# LEDMatrix_V1_0.net
KiCad netlist of a schematic drawn in EAGLE
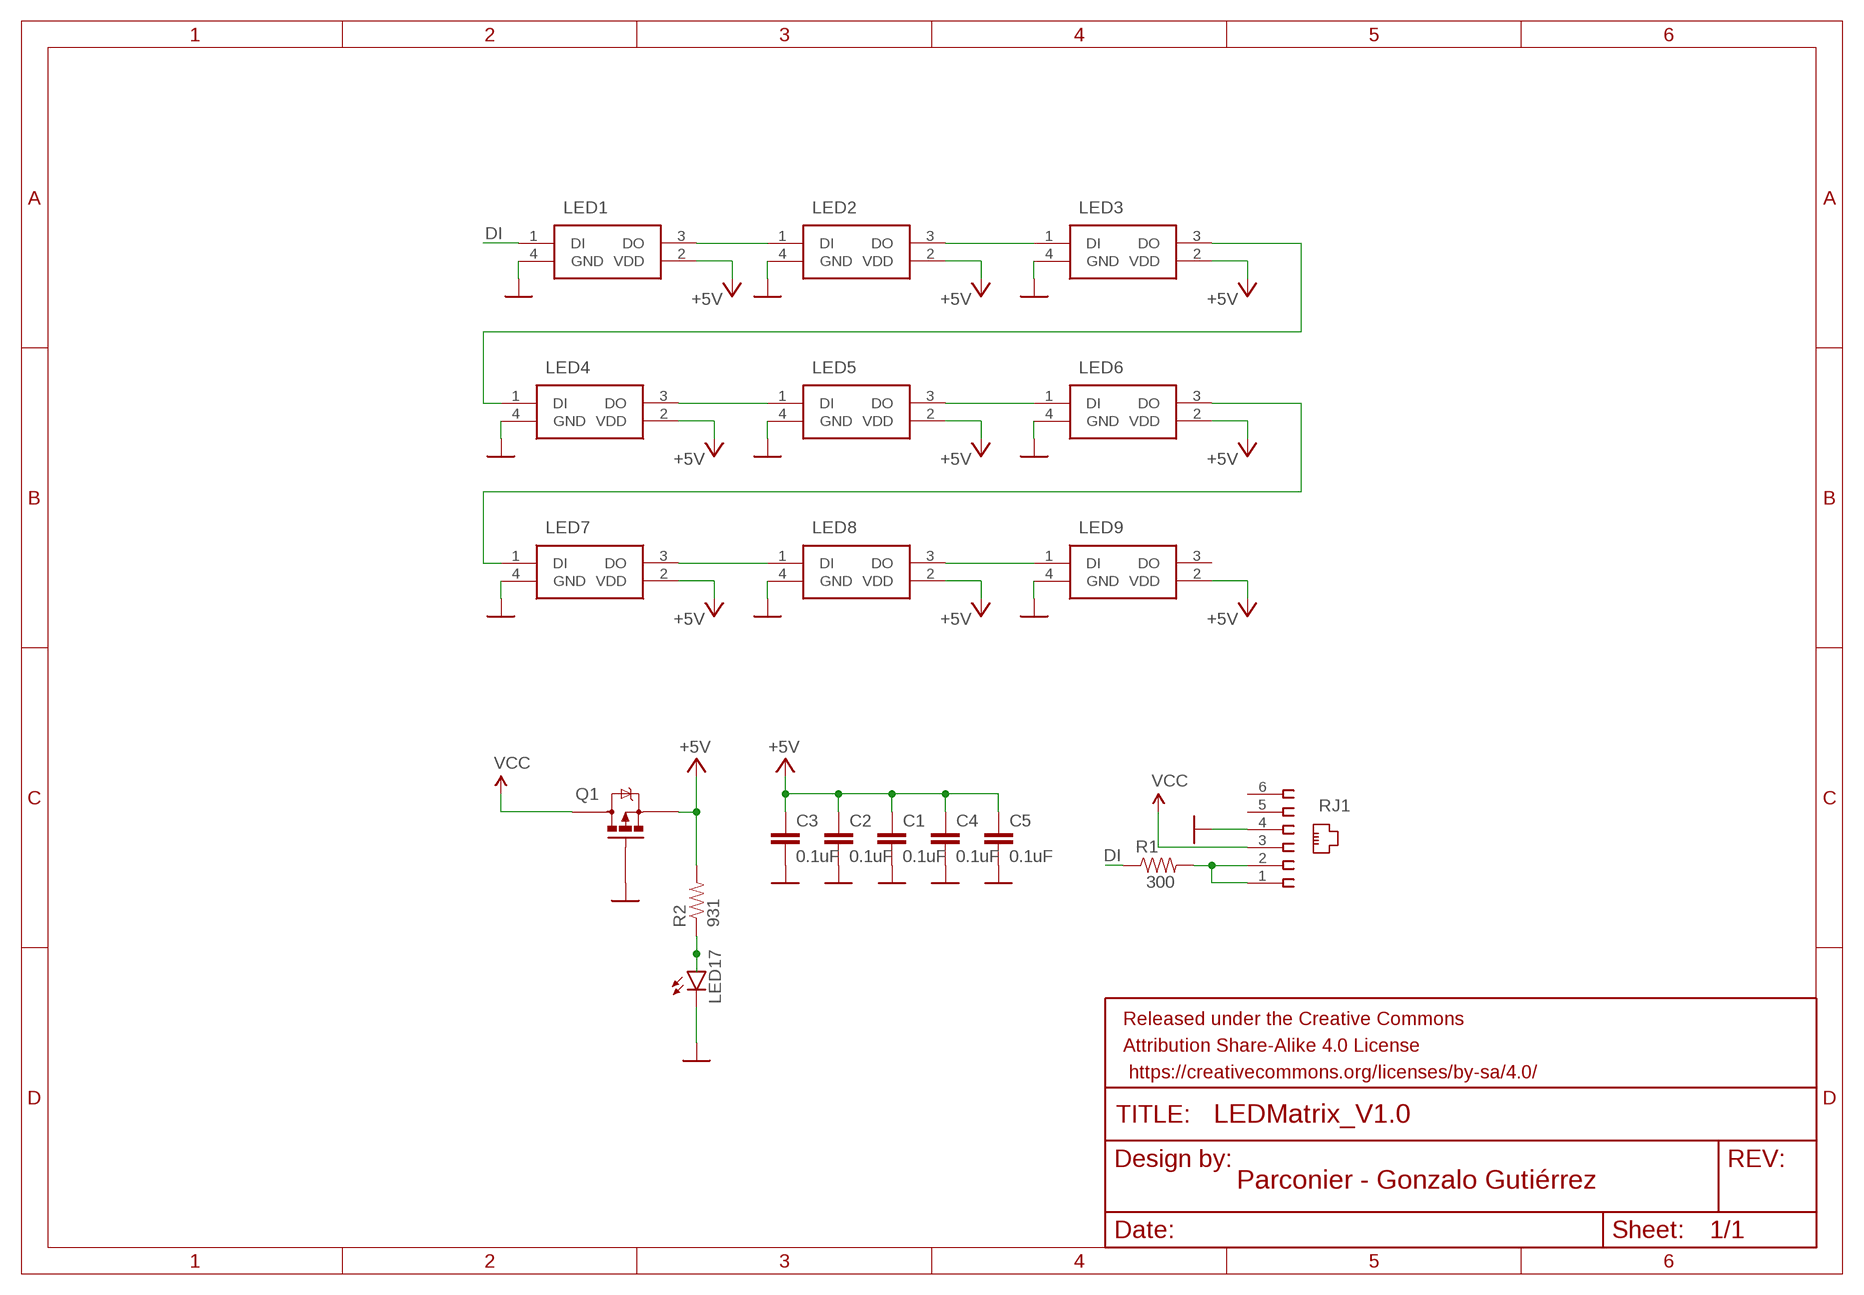
[diagram p0: schematic, sheet 1]

(export (version "E")
  (design (tool "Eeschema 10.0.6"))
  (components
    (comp (ref "C1")
      (value "0.1uF")
      (footprint "eagle-import:0402")
      (fields (field (name "MPN") "CC0402KRX5R9BB104"))
      (libsource (lib "eagle-import") (part "CAP_0402"))
    )
    (comp (ref "C2")
      (value "0.1uF")
      (footprint "eagle-import:0402")
      (fields (field (name "MPN") "CC0402KRX5R9BB104"))
      (libsource (lib "eagle-import") (part "CAP_0402"))
    )
    (comp (ref "C3")
      (value "0.1uF")
      (footprint "eagle-import:0402")
      (fields (field (name "MPN") "CC0402KRX5R9BB104"))
      (libsource (lib "eagle-import") (part "CAP_0402"))
    )
    (comp (ref "C4")
      (value "0.1uF")
      (footprint "eagle-import:0402")
      (fields (field (name "MPN") "CC0402KRX5R9BB104"))
      (libsource (lib "eagle-import") (part "CAP_0402"))
    )
    (comp (ref "C5")
      (value "0.1uF")
      (footprint "eagle-import:0402")
      (fields (field (name "MPN") "CC0402KRX5R9BB104"))
      (libsource (lib "eagle-import") (part "CAP_0402"))
    )
    (comp (ref "LED1")
      (value "SK6812MINI")
      (footprint "eagle-import:SK6812MINI")
      (fields (field (name "SPICEPREFIX") "E"))
      (libsource (lib "eagle-import") (part "SK6812MINI"))
    )
    (comp (ref "LED2")
      (value "SK6812MINI")
      (footprint "eagle-import:SK6812MINI")
      (fields (field (name "SPICEPREFIX") "E"))
      (libsource (lib "eagle-import") (part "SK6812MINI"))
    )
    (comp (ref "LED3")
      (value "SK6812MINI")
      (footprint "eagle-import:SK6812MINI")
      (fields (field (name "SPICEPREFIX") "E"))
      (libsource (lib "eagle-import") (part "SK6812MINI"))
    )
    (comp (ref "LED4")
      (value "SK6812MINI")
      (footprint "eagle-import:SK6812MINI")
      (fields (field (name "SPICEPREFIX") "E"))
      (libsource (lib "eagle-import") (part "SK6812MINI"))
    )
    (comp (ref "LED5")
      (value "SK6812MINI")
      (footprint "eagle-import:SK6812MINI")
      (fields (field (name "SPICEPREFIX") "E"))
      (libsource (lib "eagle-import") (part "SK6812MINI"))
    )
    (comp (ref "LED6")
      (value "SK6812MINI")
      (footprint "eagle-import:SK6812MINI")
      (fields (field (name "SPICEPREFIX") "E"))
      (libsource (lib "eagle-import") (part "SK6812MINI"))
    )
    (comp (ref "LED7")
      (value "SK6812MINI")
      (footprint "eagle-import:SK6812MINI")
      (fields (field (name "SPICEPREFIX") "E"))
      (libsource (lib "eagle-import") (part "SK6812MINI"))
    )
    (comp (ref "LED8")
      (value "SK6812MINI")
      (footprint "eagle-import:SK6812MINI")
      (fields (field (name "SPICEPREFIX") "E"))
      (libsource (lib "eagle-import") (part "SK6812MINI"))
    )
    (comp (ref "LED9")
      (value "SK6812MINI")
      (footprint "eagle-import:SK6812MINI")
      (fields (field (name "SPICEPREFIX") "E"))
      (libsource (lib "eagle-import") (part "SK6812MINI"))
    )
    (comp (ref "LED17")
      (value "LED0603")
      (footprint "eagle-import:LED-0603")
      (fields (field (name "MPN") "LTST-C193KRKT-5A "))
      (libsource (lib "eagle-import") (part "LED0603"))
    )
    (comp (ref "Q1")
      (value "IRLML2244TRPBF")
      (footprint "eagle-import:SOT95P237X112-3N")
      (description "HEXFET Power MOSFET")
      (fields
        (field (name "ARROW_PART_NUMBER") "IRLML2244TRPBF")
        (field (name "HEIGHT") "mm")
        (field (name "MANUFACTURER_NAME") "International Rectifier")
        (field (name "MANUFACTURER_PART_NUMBER") "IRLML2244TRPBF")
      )
      (libsource (lib "eagle-import") (part "IRLML2244TRPBF"))
    )
    (comp (ref "R1")
      (value "300")
      (footprint "eagle-import:RESC1005X35")
      (fields (field (name "MPN") "RC0402JR-07300RL"))
      (libsource (lib "eagle-import") (part "RES_0402"))
    )
    (comp (ref "R2")
      (value "931")
      (footprint "eagle-import:RESC1005X35")
      (fields (field (name "MPN") "RC0402FR-07931RL"))
      (libsource (lib "eagle-import") (part "RES_0402"))
    )
    (comp (ref "RJ1")
      (value "615006138421")
      (footprint "eagle-import:615006138421")
      (fields (field (name "RS_PART_NUMBER") "7350282"))
      (libsource (lib "eagle-import") (part "615006138421"))
    )
  )
  (nets
    (net (code "1") (name "+5V") (class "Default")
      (node (ref "C1") (pin "1") (pinfunction "1_1") (pintype "passive"))
      (node (ref "C2") (pin "1") (pinfunction "1_1") (pintype "passive"))
      (node (ref "C3") (pin "1") (pinfunction "1_1") (pintype "passive"))
      (node (ref "C4") (pin "1") (pinfunction "1_1") (pintype "passive"))
      (node (ref "C5") (pin "1") (pinfunction "1_1") (pintype "passive"))
      (node (ref "LED1") (pin "2") (pinfunction "VDD_2") (pintype "bidirectional"))
      (node (ref "LED2") (pin "2") (pinfunction "VDD_2") (pintype "bidirectional"))
      (node (ref "LED3") (pin "2") (pinfunction "VDD_2") (pintype "bidirectional"))
      (node (ref "LED4") (pin "2") (pinfunction "VDD_2") (pintype "bidirectional"))
      (node (ref "LED5") (pin "2") (pinfunction "VDD_2") (pintype "bidirectional"))
      (node (ref "LED6") (pin "2") (pinfunction "VDD_2") (pintype "bidirectional"))
      (node (ref "LED7") (pin "2") (pinfunction "VDD_2") (pintype "bidirectional"))
      (node (ref "LED8") (pin "2") (pinfunction "VDD_2") (pintype "bidirectional"))
      (node (ref "LED9") (pin "2") (pinfunction "VDD_2") (pintype "bidirectional"))
      (node (ref "Q1") (pin "2") (pinfunction "S_2") (pintype "bidirectional"))
      (node (ref "R2") (pin "2") (pinfunction "2_2") (pintype "passive"))
    )
    (net (code "2") (name "/DI") (class "Default")
      (node (ref "LED1") (pin "1") (pinfunction "DI_1") (pintype "bidirectional"))
      (node (ref "R1") (pin "1") (pinfunction "1_1") (pintype "passive"))
    )
    (net (code "3") (name "GND") (class "Default")
      (node (ref "C1") (pin "2") (pinfunction "2_2") (pintype "passive"))
      (node (ref "C2") (pin "2") (pinfunction "2_2") (pintype "passive"))
      (node (ref "C3") (pin "2") (pinfunction "2_2") (pintype "passive"))
      (node (ref "C4") (pin "2") (pinfunction "2_2") (pintype "passive"))
      (node (ref "C5") (pin "2") (pinfunction "2_2") (pintype "passive"))
      (node (ref "LED1") (pin "4") (pinfunction "GND_4") (pintype "bidirectional"))
      (node (ref "LED17") (pin "C") (pinfunction "C_C") (pintype "passive"))
      (node (ref "LED2") (pin "4") (pinfunction "GND_4") (pintype "bidirectional"))
      (node (ref "LED3") (pin "4") (pinfunction "GND_4") (pintype "bidirectional"))
      (node (ref "LED4") (pin "4") (pinfunction "GND_4") (pintype "bidirectional"))
      (node (ref "LED5") (pin "4") (pinfunction "GND_4") (pintype "bidirectional"))
      (node (ref "LED6") (pin "4") (pinfunction "GND_4") (pintype "bidirectional"))
      (node (ref "LED7") (pin "4") (pinfunction "GND_4") (pintype "bidirectional"))
      (node (ref "LED8") (pin "4") (pinfunction "GND_4") (pintype "bidirectional"))
      (node (ref "LED9") (pin "4") (pinfunction "GND_4") (pintype "bidirectional"))
      (node (ref "Q1") (pin "1") (pinfunction "G_1") (pintype "bidirectional"))
      (node (ref "RJ1") (pin "4") (pinfunction "4_4") (pintype "input"))
    )
    (net (code "4") (name "Net-(LED1-DO)") (class "Default")
      (node (ref "LED1") (pin "3") (pinfunction "DO_3") (pintype "bidirectional"))
      (node (ref "LED2") (pin "1") (pinfunction "DI_1") (pintype "bidirectional"))
    )
    (net (code "5") (name "Net-(LED2-DO)") (class "Default")
      (node (ref "LED2") (pin "3") (pinfunction "DO_3") (pintype "bidirectional"))
      (node (ref "LED3") (pin "1") (pinfunction "DI_1") (pintype "bidirectional"))
    )
    (net (code "6") (name "Net-(LED3-DO)") (class "Default")
      (node (ref "LED3") (pin "3") (pinfunction "DO_3") (pintype "bidirectional"))
      (node (ref "LED4") (pin "1") (pinfunction "DI_1") (pintype "bidirectional"))
    )
    (net (code "7") (name "Net-(LED4-DO)") (class "Default")
      (node (ref "LED4") (pin "3") (pinfunction "DO_3") (pintype "bidirectional"))
      (node (ref "LED5") (pin "1") (pinfunction "DI_1") (pintype "bidirectional"))
    )
    (net (code "8") (name "Net-(LED5-DO)") (class "Default")
      (node (ref "LED5") (pin "3") (pinfunction "DO_3") (pintype "bidirectional"))
      (node (ref "LED6") (pin "1") (pinfunction "DI_1") (pintype "bidirectional"))
    )
    (net (code "9") (name "Net-(LED6-DO)") (class "Default")
      (node (ref "LED6") (pin "3") (pinfunction "DO_3") (pintype "bidirectional"))
      (node (ref "LED7") (pin "1") (pinfunction "DI_1") (pintype "bidirectional"))
    )
    (net (code "10") (name "Net-(LED7-DO)") (class "Default")
      (node (ref "LED7") (pin "3") (pinfunction "DO_3") (pintype "bidirectional"))
      (node (ref "LED8") (pin "1") (pinfunction "DI_1") (pintype "bidirectional"))
    )
    (net (code "11") (name "Net-(LED8-DO)") (class "Default")
      (node (ref "LED8") (pin "3") (pinfunction "DO_3") (pintype "bidirectional"))
      (node (ref "LED9") (pin "1") (pinfunction "DI_1") (pintype "bidirectional"))
    )
    (net (code "12") (name "Net-(LED17-PadA)") (class "Default")
      (node (ref "LED17") (pin "A") (pinfunction "A_A") (pintype "passive"))
      (node (ref "R2") (pin "1") (pinfunction "1_1") (pintype "passive"))
    )
    (net (code "13") (name "Net-(R1-Pad2)") (class "Default")
      (node (ref "R1") (pin "2") (pinfunction "2_2") (pintype "passive"))
      (node (ref "RJ1") (pin "1") (pinfunction "1_1") (pintype "input"))
      (node (ref "RJ1") (pin "2") (pinfunction "2_2") (pintype "input"))
    )
    (net (code "14") (name "VCC") (class "Default")
      (node (ref "Q1") (pin "3") (pinfunction "D_3") (pintype "bidirectional"))
      (node (ref "RJ1") (pin "3") (pinfunction "3_3") (pintype "input"))
    )
    (net (code "15") (name "unconnected-(LED9-DO-Pad3)") (class "Default")
      (node (ref "LED9") (pin "3") (pinfunction "DO_3") (pintype "bidirectional"))
    )
    (net (code "16") (name "unconnected-(RJ1-Pad5)") (class "Default")
      (node (ref "RJ1") (pin "5") (pinfunction "5_5") (pintype "input"))
    )
    (net (code "17") (name "unconnected-(RJ1-Pad6)") (class "Default")
      (node (ref "RJ1") (pin "6") (pinfunction "6_6") (pintype "input"))
    )
  )
)
